# Power_Management.net
KiCad netlist of a schematic drawn in Altium Designer
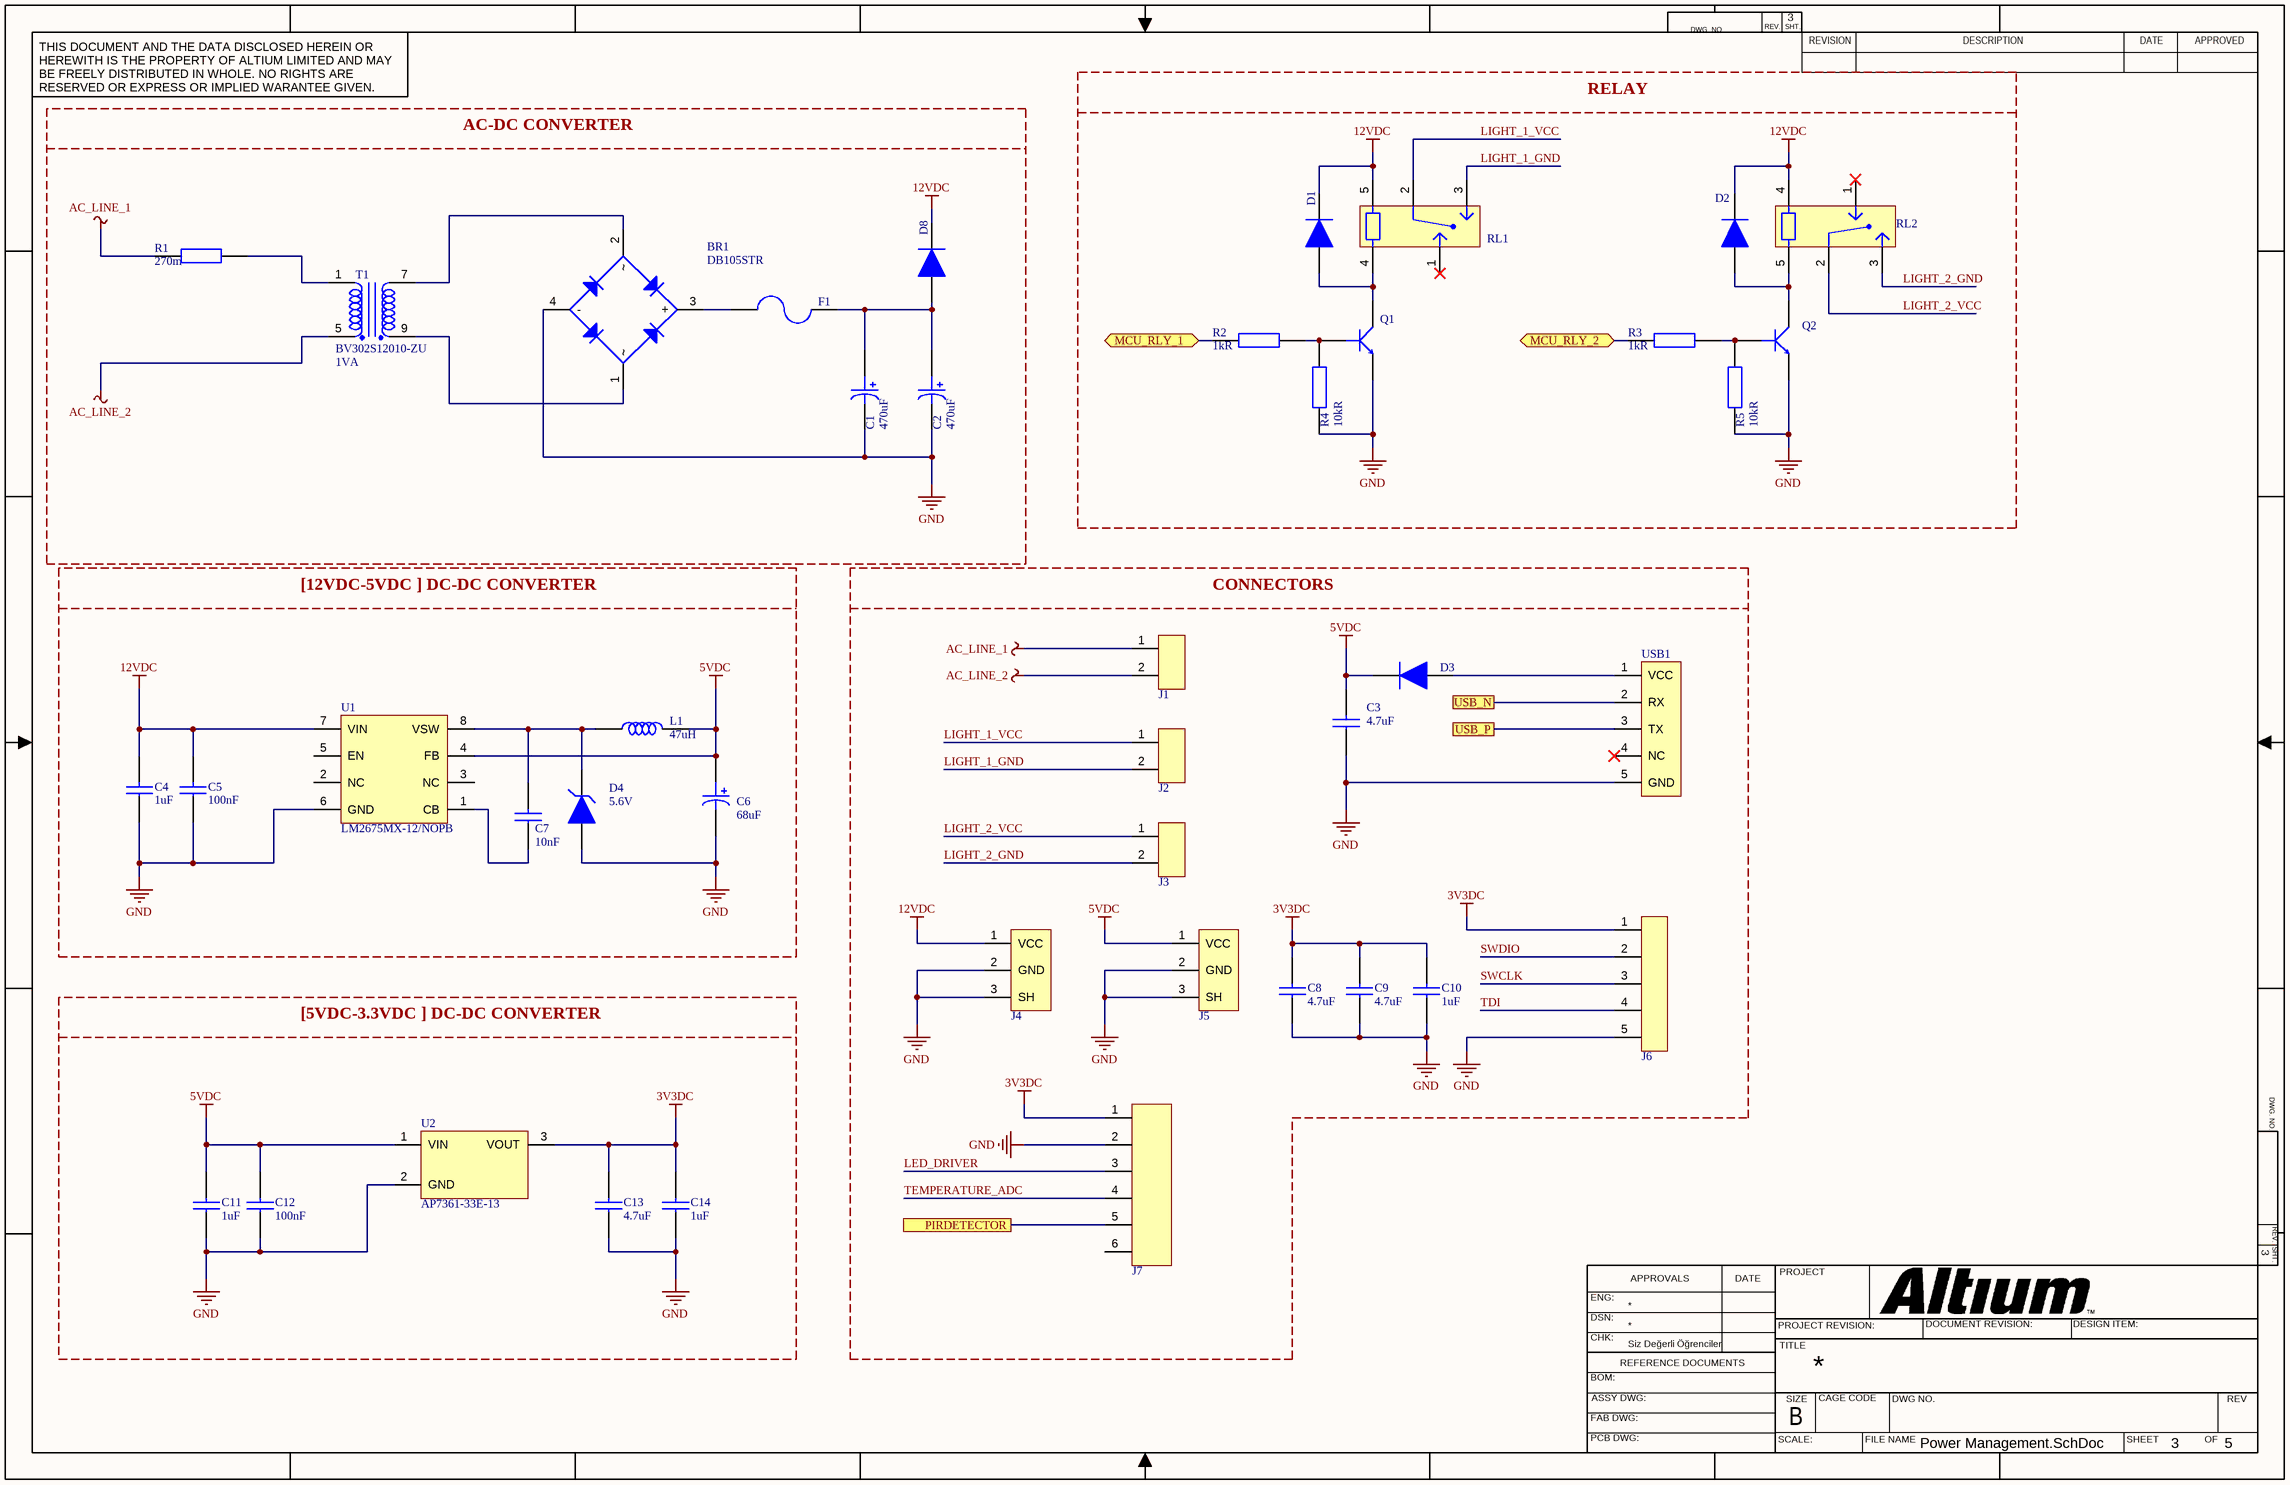
[diagram p0: Power Management.SchDoc]

(export (version "E")
  (design (tool "Eeschema 10.0.6"))
  (components
    (comp (ref "BR1")
      (value "DB105STR")
      (footprint "DB105STR")
      (description "Bridge Diode AC-DC")
      (fields (field (name "MANUFACTURER") "Sangdest Microelectronics") (field (name "DESIGNED BY") "BERK"))
      (libsource (lib "UDEMY_Library") (part "DB105STR"))
    )
    (comp (ref "C1")
      (value "ESH477M050AH4AA")
      (footprint "CAP_RADIAL_D10_P5")
      (description "CAP ALU ELEC 470uF 50V RADIAL")
      (fields
        (field (name "MANUFACTURER") "KEMET")
        (field (name "TOLERANCE") "20%")
        (field (name "CAPACITANCE") "470uF")
        (field (name "DESIGNED BY") "BERK")
      )
      (libsource (lib "UDEMY_Library") (part "CAP ALU ELEC 470uF 50V"))
    )
    (comp (ref "C2")
      (value "ESH477M050AH4AA")
      (footprint "CAP_RADIAL_D10_P5")
      (description "CAP ALU ELEC 470uF 50V RADIAL")
      (fields
        (field (name "MANUFACTURER") "KEMET")
        (field (name "TOLERANCE") "20%")
        (field (name "CAPACITANCE") "470uF")
        (field (name "DESIGNED BY") "BERK")
      )
      (libsource (lib "UDEMY_Library") (part "CAP ALU ELEC 470uF 50V"))
    )
    (comp (ref "C3")
      (value "CL21A475KAQNNNE")
      (footprint "CAP_0805")
      (description "CAP CER 4.7uF %10 0805")
      (fields
        (field (name "MANUFACTURER") "Samsung")
        (field (name "TOLERANCE") "10%")
        (field (name "CAPACITANCE") "4.7uF")
        (field (name "DESIGNED BY") "BERK")
      )
      (libsource (lib "UDEMY_Library") (part "CAP CER 4.7uF 0805"))
    )
    (comp (ref "C4")
      (value "CL21B105KBFNNNE")
      (footprint "CAP_0805")
      (description "CAP CER 1uF %10 0805")
      (fields
        (field (name "MANUFACTURER") "Samsung")
        (field (name "TOLERANCE") "10%")
        (field (name "CAPACITANCE") "1uF")
        (field (name "DESIGNED BY") "BERK")
      )
      (libsource (lib "UDEMY_Library") (part "CAP CER 1uF 0805"))
    )
    (comp (ref "C5")
      (value "CL21B104KBCNNNC")
      (footprint "CAP_0805")
      (description "CAP CER 100nF %10 0805")
      (fields
        (field (name "MANUFACTURER") "Samsung")
        (field (name "TOLERANCE") "10%")
        (field (name "CAPACITANCE") "100nF")
        (field (name "DESIGNED BY") "BERK")
      )
      (libsource (lib "UDEMY_Library") (part "CAP CER 100nF 0805"))
    )
    (comp (ref "C6")
      (value "EEV686M035A9HAA")
      (footprint "CAP_EEVseries")
      (description "Cap Aluminum Lytic 68uF 35V 20% (6.3 X 7.7mm) SMD 280mA 2000h 105C T/R")
      (fields
        (field (name "MANUFACTURER") "KEMET")
        (field (name "TOLERANCE") "20%")
        (field (name "CAPACITANCE") "68uF")
      )
      (libsource (lib "UDEMY_Library") (part "CAP ALU 68uF"))
    )
    (comp (ref "C7")
      (value "0603B103K160CT")
      (footprint "CAP_0603")
      (description "CAP CER 10nF %10 0603")
      (fields
        (field (name "MANUFACTURER") "Walsin Technologies")
        (field (name "TOLERANCE") "10%")
        (field (name "CAPACITANCE") "10nF")
        (field (name "DESIGNED BY") "BERK")
      )
      (libsource (lib "UDEMY_Library") (part "CAP CER 10nF 0603"))
    )
    (comp (ref "C8")
      (value "CL21A475KAQNNNE")
      (footprint "CAP_0805")
      (description "CAP CER 4.7uF %10 0805")
      (fields
        (field (name "MANUFACTURER") "Samsung")
        (field (name "TOLERANCE") "10%")
        (field (name "CAPACITANCE") "4.7uF")
        (field (name "DESIGNED BY") "BERK")
      )
      (libsource (lib "UDEMY_Library") (part "CAP CER 4.7uF 0805"))
    )
    (comp (ref "C9")
      (value "CL21A475KAQNNNE")
      (footprint "CAP_0805")
      (description "CAP CER 4.7uF %10 0805")
      (fields
        (field (name "MANUFACTURER") "Samsung")
        (field (name "TOLERANCE") "10%")
        (field (name "CAPACITANCE") "4.7uF")
        (field (name "DESIGNED BY") "BERK")
      )
      (libsource (lib "UDEMY_Library") (part "CAP CER 4.7uF 0805"))
    )
    (comp (ref "C10")
      (value "CL21B105KBFNNNE")
      (footprint "CAP_0805")
      (description "CAP CER 1uF %10 0805")
      (fields
        (field (name "MANUFACTURER") "Samsung")
        (field (name "TOLERANCE") "10%")
        (field (name "CAPACITANCE") "1uF")
        (field (name "DESIGNED BY") "BERK")
      )
      (libsource (lib "UDEMY_Library") (part "CAP CER 1uF 0805"))
    )
    (comp (ref "C11")
      (value "CL21B105KBFNNNE")
      (footprint "CAP_0805")
      (description "CAP CER 1uF %10 0805")
      (fields
        (field (name "MANUFACTURER") "Samsung")
        (field (name "TOLERANCE") "10%")
        (field (name "CAPACITANCE") "1uF")
        (field (name "DESIGNED BY") "BERK")
      )
      (libsource (lib "UDEMY_Library") (part "CAP CER 1uF 0805"))
    )
    (comp (ref "C12")
      (value "C0603C104K5RACTU")
      (footprint "CAP_0603")
      (description "CAP CER 100nF %10 0603 SMD")
      (fields
        (field (name "MANUFACTURER") "KEMET")
        (field (name "TOLERANCE") "10%")
        (field (name "CAPACITANCE") "100nF")
        (field (name "DESIGNED BY") "BERK")
      )
      (libsource (lib "UDEMY_Library") (part "CAP CER 100nF 0603"))
    )
    (comp (ref "C13")
      (value "CL21A475KAQNNNE")
      (footprint "CAP_0805")
      (description "CAP CER 4.7uF %10 0805")
      (fields
        (field (name "MANUFACTURER") "Samsung")
        (field (name "TOLERANCE") "10%")
        (field (name "CAPACITANCE") "4.7uF")
        (field (name "DESIGNED BY") "BERK")
      )
      (libsource (lib "UDEMY_Library") (part "CAP CER 4.7uF 0805"))
    )
    (comp (ref "C14")
      (value "CL21B105KBFNNNE")
      (footprint "CAP_0805")
      (description "CAP CER 1uF %10 0805")
      (fields
        (field (name "MANUFACTURER") "Samsung")
        (field (name "TOLERANCE") "10%")
        (field (name "CAPACITANCE") "1uF")
        (field (name "DESIGNED BY") "BERK")
      )
      (libsource (lib "UDEMY_Library") (part "CAP CER 1uF 0805"))
    )
    (comp (ref "D1")
      (value "1N4148WS")
      (footprint "SOD323F")
      (description "Diode, Single, 75 V, 150 mA, 1 V, 4 ns")
      (fields
        (field (name "MANUFACTURER") "ON Semiconductor / Fairchild")
        (field (name "DESIGNED BY") "BERK")
      )
      (libsource (lib "UDEMY_Library") (part "1N4148WS"))
    )
    (comp (ref "D2")
      (value "1N4148WS")
      (footprint "SOD323F")
      (description "Diode, Single, 75 V, 150 mA, 1 V, 4 ns")
      (fields
        (field (name "MANUFACTURER") "ON Semiconductor / Fairchild")
        (field (name "DESIGNED BY") "BERK")
      )
      (libsource (lib "UDEMY_Library") (part "1N4148WS"))
    )
    (comp (ref "D3")
      (value "1N4148WS")
      (footprint "SOD323F")
      (description "Diode, Single, 75 V, 150 mA, 1 V, 4 ns")
      (fields
        (field (name "MANUFACTURER") "ON Semiconductor / Fairchild")
        (field (name "DESIGNED BY") "BERK")
      )
      (libsource (lib "UDEMY_Library") (part "1N4148WS"))
    )
    (comp (ref "D4")
      (value "1SMB5919BT3G")
      (footprint "SMB")
      (description "Diode Zener Single 5.6V 5% 3W 2-Pin SMB T/R")
      (fields
        (field (name "MANUFACTURER") "ON Semiconductor")
        (field (name "TOLERANCE") "5%")
        (field (name "WORKING VOLTAGE") "5.6V")
        (field (name "DESIGNED BY") "BERK")
      )
      (libsource (lib "UDEMY_Library") (part "1SMB5919BT3G"))
    )
    (comp (ref "D8")
      (value "1N4148WS")
      (footprint "SOD323F")
      (description "Diode, Single, 75 V, 150 mA, 1 V, 4 ns")
      (fields
        (field (name "MANUFACTURER") "ON Semiconductor / Fairchild")
        (field (name "DESIGNED BY") "BERK")
      )
      (libsource (lib "UDEMY_Library") (part "1N4148WS"))
    )
    (comp (ref "F1")
      (value "3413.0216.22")
      (footprint "3413.0216.22")
      (description "FUSE BRD MNT 1A 32VAC 63VDC 1206")
      (fields (field (name "MANUFACTURER") "Schurter") (field (name "DESIGNED BY") "BERK"))
      (libsource (lib "UDEMY_Library") (part "FUSE 3413.0216.22"))
    )
    (comp (ref "J1")
      (value "TBP01R1-508-02BE")
      (footprint "TBP01R1-508")
      (description "Conn Shrouded Header HDR 2 POS 5.08mm Solder RA Side Entry Thru-Hole Bag")
      (fields (field (name "MANUFACTURER") "CUI") (field (name "DESIGNED BY") "BERK"))
      (libsource (lib "UDEMY_Library") (part "TBP01R1-508-02BE"))
    )
    (comp (ref "J2")
      (value "TBP01R1-508-02BE")
      (footprint "TBP01R1-508")
      (description "Conn Shrouded Header HDR 2 POS 5.08mm Solder RA Side Entry Thru-Hole Bag")
      (fields (field (name "MANUFACTURER") "CUI") (field (name "DESIGNED BY") "BERK"))
      (libsource (lib "UDEMY_Library") (part "TBP01R1-508-02BE"))
    )
    (comp (ref "J3")
      (value "TBP01R1-508-02BE")
      (footprint "TBP01R1-508")
      (description "Conn Shrouded Header HDR 2 POS 5.08mm Solder RA Side Entry Thru-Hole Bag")
      (fields (field (name "MANUFACTURER") "CUI") (field (name "DESIGNED BY") "BERK"))
      (libsource (lib "UDEMY_Library") (part "TBP01R1-508-02BE"))
    )
    (comp (ref "J4")
      (value "PJ-037AH-SMT-TR")
      (footprint "JACK")
      (description "DC Power Connectors Power Jacks")
      (fields (field (name "MANUFACTURER") "CUI") (field (name "DESIGNED BY") "BERK"))
      (libsource (lib "UDEMY_Library") (part "PJ-037AH-SMT-TR"))
    )
    (comp (ref "J5")
      (value "PJ-037AH-SMT-TR")
      (footprint "JACK")
      (description "DC Power Connectors Power Jacks")
      (fields (field (name "MANUFACTURER") "CUI") (field (name "DESIGNED BY") "BERK"))
      (libsource (lib "UDEMY_Library") (part "PJ-037AH-SMT-TR"))
    )
    (comp (ref "J6")
      (value "SMH-105-02-L-S")
      (footprint "PINHEADER1X5_RA")
      (description ".100 C.L. HORIZONTAL SMT SOCKET")
      (fields (field (name "MANUFACTURER") "Samtec") (field (name "DESIGNED BY") "BERK"))
      (libsource (lib "UDEMY_Library") (part "SMH-105-02-L-S"))
    )
    (comp (ref "J7")
      (value "64800611622")
      (footprint "64800611622")
      (description "1.50mm 6PIN Connector")
      (fields (field (name "MANUFACTURER") "Wurth Electronics"))
      (libsource (lib "UDEMY_Library") (part "64800611622_conn_6pin"))
    )
    (comp (ref "L1")
      (value "78438335470")
      (footprint "IND_1212")
      (description "FIXED IND 47UH 390MA 2.3 OHM SMD")
      (fields
        (field (name "MANUFACTURER") "Wurth Electronics")
        (field (name "TOLERANCE") "30%")
        (field (name "INDUCTANCE") "47uH")
        (field (name "DESIGNED BY") "BERK")
      )
      (libsource (lib "UDEMY_Library") (part "IND 47uH"))
    )
    (comp (ref "Q1")
      (value "MMBT3904-7-F")
      (footprint "SOT-23F")
      (description "Transistor General Purpose BJT NPN 40 Volt 0.2A Automotive 3-Pin SOT-23")
      (fields (field (name "MANUFACTURER") "Diodes Zetex") (field (name "DESIGNED BY") "BERK"))
      (libsource (lib "UDEMY_Library") (part "MMBT3904-7-F"))
    )
    (comp (ref "Q2")
      (value "MMBT3904-7-F")
      (footprint "SOT-23F")
      (description "Transistor General Purpose BJT NPN 40 Volt 0.2A Automotive 3-Pin SOT-23")
      (fields (field (name "MANUFACTURER") "Diodes Zetex") (field (name "DESIGNED BY") "BERK"))
      (libsource (lib "UDEMY_Library") (part "MMBT3904-7-F"))
    )
    (comp (ref "R1")
      (value "5WD27")
      (footprint "RES_AXIAL_W")
      (description "Resistor 5 Watt Cermet Wirewound Flameproof .27 Ohm 5% Axial Lead")
      (fields
        (field (name "MANUFACTURER") "NTE Electronics")
        (field (name "TOLERANCE") "5%")
        (field (name "RESISTANCE") "270m")
        (field (name "DESIGNED BY") "BERK")
      )
      (libsource (lib "UDEMY_Library") (part "5WD27"))
    )
    (comp (ref "R2")
      (value "RC0603FR-0710KL")
      (footprint "RES_0603")
      (description "RES 1K %1 OHM 0603 SMD")
      (fields
        (field (name "MANUFACTURER") "Yageo")
        (field (name "MANUFACTURER PART NUMBER") "RC0603JR-071KL")
        (field (name "RESISTANCE") "1kR")
        (field (name "DESIGNED BY") "BERK")
      )
      (libsource (lib "UDEMY_Library") (part "RES 1K OHM 0603"))
    )
    (comp (ref "R3")
      (value "RC0603FR-0710KL")
      (footprint "RES_0603")
      (description "RES 1K %1 OHM 0603 SMD")
      (fields
        (field (name "MANUFACTURER") "Yageo")
        (field (name "MANUFACTURER PART NUMBER") "RC0603JR-071KL")
        (field (name "RESISTANCE") "1kR")
        (field (name "DESIGNED BY") "BERK")
      )
      (libsource (lib "UDEMY_Library") (part "RES 1K OHM 0603"))
    )
    (comp (ref "R4")
      (value "RC0603FR-0710KL")
      (footprint "RES_0603")
      (description "RES 10K %1 OHM 0603 SMD")
      (fields
        (field (name "MANUFACTURER") "Yageo")
        (field (name "TOLERANCE") "1%")
        (field (name "RESISTANCE") "10kR")
        (field (name "DESIGNED BY") "BERK")
      )
      (libsource (lib "UDEMY_Library") (part "RES 10K OHM 0603"))
    )
    (comp (ref "R5")
      (value "RC0603FR-0710KL")
      (footprint "RES_0603")
      (description "RES 10K %1 OHM 0603 SMD")
      (fields
        (field (name "MANUFACTURER") "Yageo")
        (field (name "TOLERANCE") "1%")
        (field (name "RESISTANCE") "10kR")
        (field (name "DESIGNED BY") "BERK")
      )
      (libsource (lib "UDEMY_Library") (part "RES 10K OHM 0603"))
    )
    (comp (ref "RL1")
      (value "ALQ112")
      (footprint "ALQ112")
      (description "General Purpose Relay SPDT (1 Form C) 12VDC Coil Through Hole")
      (fields (field (name "MANUFACTURER") "Panasonic") (field (name "DESIGNED BY") "BERK"))
      (libsource (lib "UDEMY_Library") (part "ALQ112"))
    )
    (comp (ref "RL2")
      (value "ALQ112")
      (footprint "ALQ112")
      (description "General Purpose Relay SPDT (1 Form C) 12VDC Coil Through Hole")
      (fields (field (name "MANUFACTURER") "Panasonic") (field (name "DESIGNED BY") "BERK"))
      (libsource (lib "") (part "ALQ112_1"))
    )
    (comp (ref "T1")
      (value "BV302S12010-ZU")
      (footprint "BV302S")
      (description "230-12 Transformer 1VA")
      (fields
        (field (name "MANUFACTURER") "Zettler Magnetics")
        (field (name "RATED POWER") "1VA")
        (field (name "DESIGNED BY") "BERK")
      )
      (libsource (lib "UDEMY_Library") (part "BV302S12010-ZU"))
    )
    (comp (ref "U1")
      (value "LM2675MX-12/NOPB")
      (footprint "SOIC8")
      (description "Switching Voltage Regulators Pwr Cnvtr Hi Eff 1A SD Vtg Reg")
      (fields (field (name "MANUFACTURER") "TI National Semiconductor") (field (name "DESIGNED BY") "BERK"))
      (libsource (lib "UDEMY_Library") (part "LM2675MX-12/NOPB"))
    )
    (comp (ref "U2")
      (value "AP7361-33E-13")
      (footprint "SOT223")
      (description "LDO Regulator Pos 3.3V 1A 4-Pin(3+Tab) SOT-223 T/R")
      (fields (field (name "MANUFACTURER") "Diodes") (field (name "DESIGNED BY") "BERK"))
      (libsource (lib "UDEMY_Library") (part "AP7361-33E-13"))
    )
    (comp (ref "USB1")
      (value "10118192-0001LF")
      (footprint "MICRO_B_USB")
      (description "CONN RCPT USB2.0 MICRO B SMD R/A")
      (fields (field (name "MANUFACTURER") "Amphenol FCI") (field (name "DESIGNED BY") "BERK"))
      (libsource (lib "UDEMY_Library") (part "Micro B USB Connector"))
    )
  )
  (nets
    (net (code "1") (name "/LED_DRIVER") (class "Default") (node (ref "J7") (pin "3") (pintype "power_in")))
    (net (code "2") (name "/LIGHT_1_GND") (class "Default")
      (node (ref "J2") (pin "2") (pinfunction "2_2") (pintype "power_in"))
      (node (ref "RL1") (pin "3") (pinfunction "3_3") (pintype "passive"))
    )
    (net (code "3") (name "/LIGHT_1_VCC") (class "Default")
      (node (ref "J2") (pin "1") (pinfunction "1_1") (pintype "power_in"))
      (node (ref "RL1") (pin "2") (pinfunction "2_2") (pintype "passive"))
    )
    (net (code "4") (name "/LIGHT_2_GND") (class "Default")
      (node (ref "J3") (pin "2") (pinfunction "2_2") (pintype "power_in"))
      (node (ref "RL2") (pin "3") (pinfunction "3_3") (pintype "passive"))
    )
    (net (code "5") (name "/LIGHT_2_VCC") (class "Default")
      (node (ref "J3") (pin "1") (pinfunction "1_1") (pintype "power_in"))
      (node (ref "RL2") (pin "2") (pinfunction "2_2") (pintype "passive"))
    )
    (net (code "6") (name "/MCU_RLY_1") (class "Default")
      (node (ref "R2") (pin "1") (pinfunction "1_1") (pintype "passive"))
    )
    (net (code "7") (name "/MCU_RLY_2") (class "Default")
      (node (ref "R3") (pin "1") (pinfunction "1_1") (pintype "passive"))
    )
    (net (code "8") (name "/PIRDETECTOR") (class "Default") (node (ref "J7") (pin "5") (pintype "power_in")))
    (net (code "9") (name "/SWCLK") (class "Default")
      (node (ref "J6") (pin "3") (pinfunction "3_3") (pintype "power_in"))
    )
    (net (code "10") (name "/SWDIO") (class "Default")
      (node (ref "J6") (pin "2") (pinfunction "2_2") (pintype "power_in"))
    )
    (net (code "11") (name "/TDI") (class "Default")
      (node (ref "J6") (pin "4") (pinfunction "4_4") (pintype "power_in"))
    )
    (net (code "12") (name "/TEMPERATURE_ADC") (class "Default")
      (node (ref "J7") (pin "4") (pintype "power_in"))
    )
    (net (code "13") (name "/USB_N") (class "Default")
      (node (ref "USB1") (pin "2") (pinfunction "RX_2") (pintype "power_in"))
    )
    (net (code "14") (name "/USB_P") (class "Default")
      (node (ref "USB1") (pin "3") (pinfunction "TX_3") (pintype "power_in"))
    )
    (net (code "15") (name "3V3DC") (class "Default")
      (node (ref "C10") (pin "2") (pinfunction "2_2") (pintype "passive"))
      (node (ref "C13") (pin "2") (pinfunction "2_2") (pintype "passive"))
      (node (ref "C14") (pin "2") (pinfunction "2_2") (pintype "passive"))
      (node (ref "C8") (pin "2") (pinfunction "2_2") (pintype "passive"))
      (node (ref "C9") (pin "2") (pinfunction "2_2") (pintype "passive"))
      (node (ref "J6") (pin "1") (pinfunction "1_1") (pintype "power_in"))
      (node (ref "J7") (pin "1") (pintype "power_in"))
      (node (ref "U2") (pin "3") (pinfunction "VOUT_3") (pintype "passive"))
    )
    (net (code "16") (name "5VDC") (class "Default")
      (node (ref "C11") (pin "2") (pinfunction "2_2") (pintype "passive"))
      (node (ref "C12") (pin "2") (pinfunction "2_2") (pintype "passive"))
      (node (ref "C3") (pin "2") (pinfunction "2_2") (pintype "passive"))
      (node (ref "C6") (pin "1") (pinfunction "1_1") (pintype "passive"))
      (node (ref "D3") (pin "1") (pinfunction "1_1") (pintype "power_in"))
      (node (ref "J5") (pin "1") (pinfunction "VCC_1") (pintype "power_in"))
      (node (ref "L1") (pin "2") (pinfunction "2_2") (pintype "passive"))
      (node (ref "U1") (pin "4") (pinfunction "FB_4") (pintype "passive"))
      (node (ref "U2") (pin "1") (pinfunction "VIN_1") (pintype "passive"))
    )
    (net (code "17") (name "12VDC") (class "Default")
      (node (ref "C4") (pin "2") (pinfunction "2_2") (pintype "passive"))
      (node (ref "C5") (pin "2") (pinfunction "2_2") (pintype "passive"))
      (node (ref "D1") (pin "1") (pinfunction "1_1") (pintype "power_in"))
      (node (ref "D2") (pin "1") (pinfunction "1_1") (pintype "power_in"))
      (node (ref "D8") (pin "1") (pinfunction "1_1") (pintype "power_in"))
      (node (ref "J4") (pin "1") (pinfunction "VCC_1") (pintype "power_in"))
      (node (ref "RL1") (pin "5") (pinfunction "5_5") (pintype "passive"))
      (node (ref "RL2") (pin "4") (pinfunction "4_4") (pintype "passive"))
      (node (ref "U1") (pin "7") (pinfunction "VIN_7") (pintype "passive"))
    )
    (net (code "18") (name "AC_LINE_1") (class "Default")
      (node (ref "J1") (pin "1") (pinfunction "1_1") (pintype "power_in"))
      (node (ref "R1") (pin "1") (pinfunction "1_1") (pintype "passive"))
    )
    (net (code "19") (name "AC_LINE_2") (class "Default")
      (node (ref "J1") (pin "2") (pinfunction "2_2") (pintype "power_in"))
      (node (ref "T1") (pin "5") (pinfunction "5_5") (pintype "passive"))
    )
    (net (code "20") (name "GND") (class "Default")
      (node (ref "BR1") (pin "4") (pinfunction "-_4") (pintype "passive"))
      (node (ref "C1") (pin "2") (pinfunction "2_2") (pintype "passive"))
      (node (ref "C10") (pin "1") (pinfunction "1_1") (pintype "passive"))
      (node (ref "C11") (pin "1") (pinfunction "1_1") (pintype "passive"))
      (node (ref "C12") (pin "1") (pinfunction "1_1") (pintype "passive"))
      (node (ref "C13") (pin "1") (pinfunction "1_1") (pintype "passive"))
      (node (ref "C14") (pin "1") (pinfunction "1_1") (pintype "passive"))
      (node (ref "C2") (pin "2") (pinfunction "2_2") (pintype "passive"))
      (node (ref "C3") (pin "1") (pinfunction "1_1") (pintype "passive"))
      (node (ref "C4") (pin "1") (pinfunction "1_1") (pintype "passive"))
      (node (ref "C5") (pin "1") (pinfunction "1_1") (pintype "passive"))
      (node (ref "C6") (pin "2") (pinfunction "2_2") (pintype "passive"))
      (node (ref "C8") (pin "1") (pinfunction "1_1") (pintype "passive"))
      (node (ref "C9") (pin "1") (pinfunction "1_1") (pintype "passive"))
      (node (ref "D4") (pin "A") (pinfunction "A_A") (pintype "passive"))
      (node (ref "J4") (pin "2") (pinfunction "GND_2") (pintype "power_in"))
      (node (ref "J4") (pin "3") (pinfunction "SH_3") (pintype "power_in"))
      (node (ref "J5") (pin "2") (pinfunction "GND_2") (pintype "power_in"))
      (node (ref "J5") (pin "3") (pinfunction "SH_3") (pintype "power_in"))
      (node (ref "J6") (pin "5") (pinfunction "5_5") (pintype "power_in"))
      (node (ref "J7") (pin "2") (pintype "power_in"))
      (node (ref "Q1") (pin "2") (pinfunction "E_2") (pintype "power_in"))
      (node (ref "Q2") (pin "2") (pinfunction "E_2") (pintype "power_in"))
      (node (ref "R4") (pin "1") (pinfunction "1_1") (pintype "passive"))
      (node (ref "R5") (pin "1") (pinfunction "1_1") (pintype "passive"))
      (node (ref "U1") (pin "6") (pinfunction "GND_6") (pintype "passive"))
      (node (ref "U2") (pin "2") (pinfunction "GND_2") (pintype "passive"))
      (node (ref "USB1") (pin "5") (pinfunction "GND_5") (pintype "power_in"))
    )
    (net (code "21") (name "Net-(BR1-+)") (class "Default")
      (node (ref "BR1") (pin "3") (pinfunction "+_3") (pintype "passive"))
      (node (ref "F1") (pin "1") (pinfunction "1_1") (pintype "passive"))
    )
    (net (code "22") (name "Net-(BR1-~-Pad1)") (class "Default")
      (node (ref "BR1") (pin "1") (pinfunction "~_1") (pintype "passive"))
      (node (ref "T1") (pin "9") (pinfunction "9_9") (pintype "passive"))
    )
    (net (code "23") (name "Net-(BR1-~-Pad2)") (class "Default")
      (node (ref "BR1") (pin "2") (pinfunction "~_2") (pintype "passive"))
      (node (ref "T1") (pin "7") (pinfunction "7_7") (pintype "passive"))
    )
    (net (code "24") (name "Net-(C1-Pad1)") (class "Default")
      (node (ref "C1") (pin "1") (pinfunction "1_1") (pintype "passive"))
      (node (ref "C2") (pin "1") (pinfunction "1_1") (pintype "passive"))
      (node (ref "D8") (pin "2") (pinfunction "2_2") (pintype "power_in"))
      (node (ref "F1") (pin "2") (pinfunction "2_2") (pintype "passive"))
    )
    (net (code "25") (name "Net-(Q1-B)") (class "Default")
      (node (ref "Q1") (pin "1") (pinfunction "B_1") (pintype "power_in"))
      (node (ref "R2") (pin "2") (pinfunction "2_2") (pintype "passive"))
      (node (ref "R4") (pin "2") (pinfunction "2_2") (pintype "passive"))
    )
    (net (code "26") (name "Net-(Q1-C)") (class "Default")
      (node (ref "D1") (pin "2") (pinfunction "2_2") (pintype "power_in"))
      (node (ref "Q1") (pin "3") (pinfunction "C_3") (pintype "power_in"))
      (node (ref "RL1") (pin "4") (pinfunction "4_4") (pintype "passive"))
    )
    (net (code "27") (name "Net-(Q2-B)") (class "Default")
      (node (ref "Q2") (pin "1") (pinfunction "B_1") (pintype "power_in"))
      (node (ref "R3") (pin "2") (pinfunction "2_2") (pintype "passive"))
      (node (ref "R5") (pin "2") (pinfunction "2_2") (pintype "passive"))
    )
    (net (code "28") (name "Net-(Q2-C)") (class "Default")
      (node (ref "D2") (pin "2") (pinfunction "2_2") (pintype "power_in"))
      (node (ref "Q2") (pin "3") (pinfunction "C_3") (pintype "power_in"))
      (node (ref "RL2") (pin "5") (pinfunction "5_5") (pintype "passive"))
    )
    (net (code "29") (name "Net-(R1-Pad2)") (class "Default")
      (node (ref "R1") (pin "2") (pinfunction "2_2") (pintype "passive"))
      (node (ref "T1") (pin "1") (pinfunction "1_1") (pintype "passive"))
    )
    (net (code "30") (name "Net-(U1-CB)") (class "Default")
      (node (ref "C7") (pin "1") (pinfunction "1_1") (pintype "passive"))
      (node (ref "U1") (pin "1") (pinfunction "CB_1") (pintype "passive"))
    )
    (net (code "31") (name "Net-(U1-VSW)") (class "Default")
      (node (ref "C7") (pin "2") (pinfunction "2_2") (pintype "passive"))
      (node (ref "D4") (pin "C") (pinfunction "C_C") (pintype "passive"))
      (node (ref "L1") (pin "1") (pinfunction "1_1") (pintype "passive"))
      (node (ref "U1") (pin "8") (pinfunction "VSW_8") (pintype "passive"))
    )
    (net (code "32") (name "Net-(USB1-VCC)") (class "Default")
      (node (ref "D3") (pin "2") (pinfunction "2_2") (pintype "power_in"))
      (node (ref "USB1") (pin "1") (pinfunction "VCC_1") (pintype "power_in"))
    )
    (net (code "33") (name "unconnected-(J7-Pad6)") (class "Default")
      (node (ref "J7") (pin "6") (pintype "power_in"))
    )
    (net (code "34") (name "unconnected-(RL1-Pad1)") (class "Default")
      (node (ref "RL1") (pin "1") (pinfunction "1_1") (pintype "passive+no_connect"))
    )
    (net (code "35") (name "unconnected-(RL2-Pad1)") (class "Default")
      (node (ref "RL2") (pin "1") (pinfunction "1_1") (pintype "passive+no_connect"))
    )
    (net (code "36") (name "unconnected-(U1-EN-Pad5)") (class "Default")
      (node (ref "U1") (pin "5") (pinfunction "EN_5") (pintype "passive"))
    )
    (net (code "37") (name "unconnected-(U1-NC-Pad2)") (class "Default")
      (node (ref "U1") (pin "2") (pinfunction "NC_2") (pintype "passive"))
    )
    (net (code "38") (name "unconnected-(U1-NC-Pad3)") (class "Default")
      (node (ref "U1") (pin "3") (pinfunction "NC_3") (pintype "passive"))
    )
    (net (code "39") (name "unconnected-(USB1-NC-Pad4)") (class "Default")
      (node (ref "USB1") (pin "4") (pinfunction "NC_4") (pintype "power_in+no_connect"))
    )
  )
)
